# 07_mPCIe_4-8.net
KiCad netlist of a schematic drawn in Altium Designer
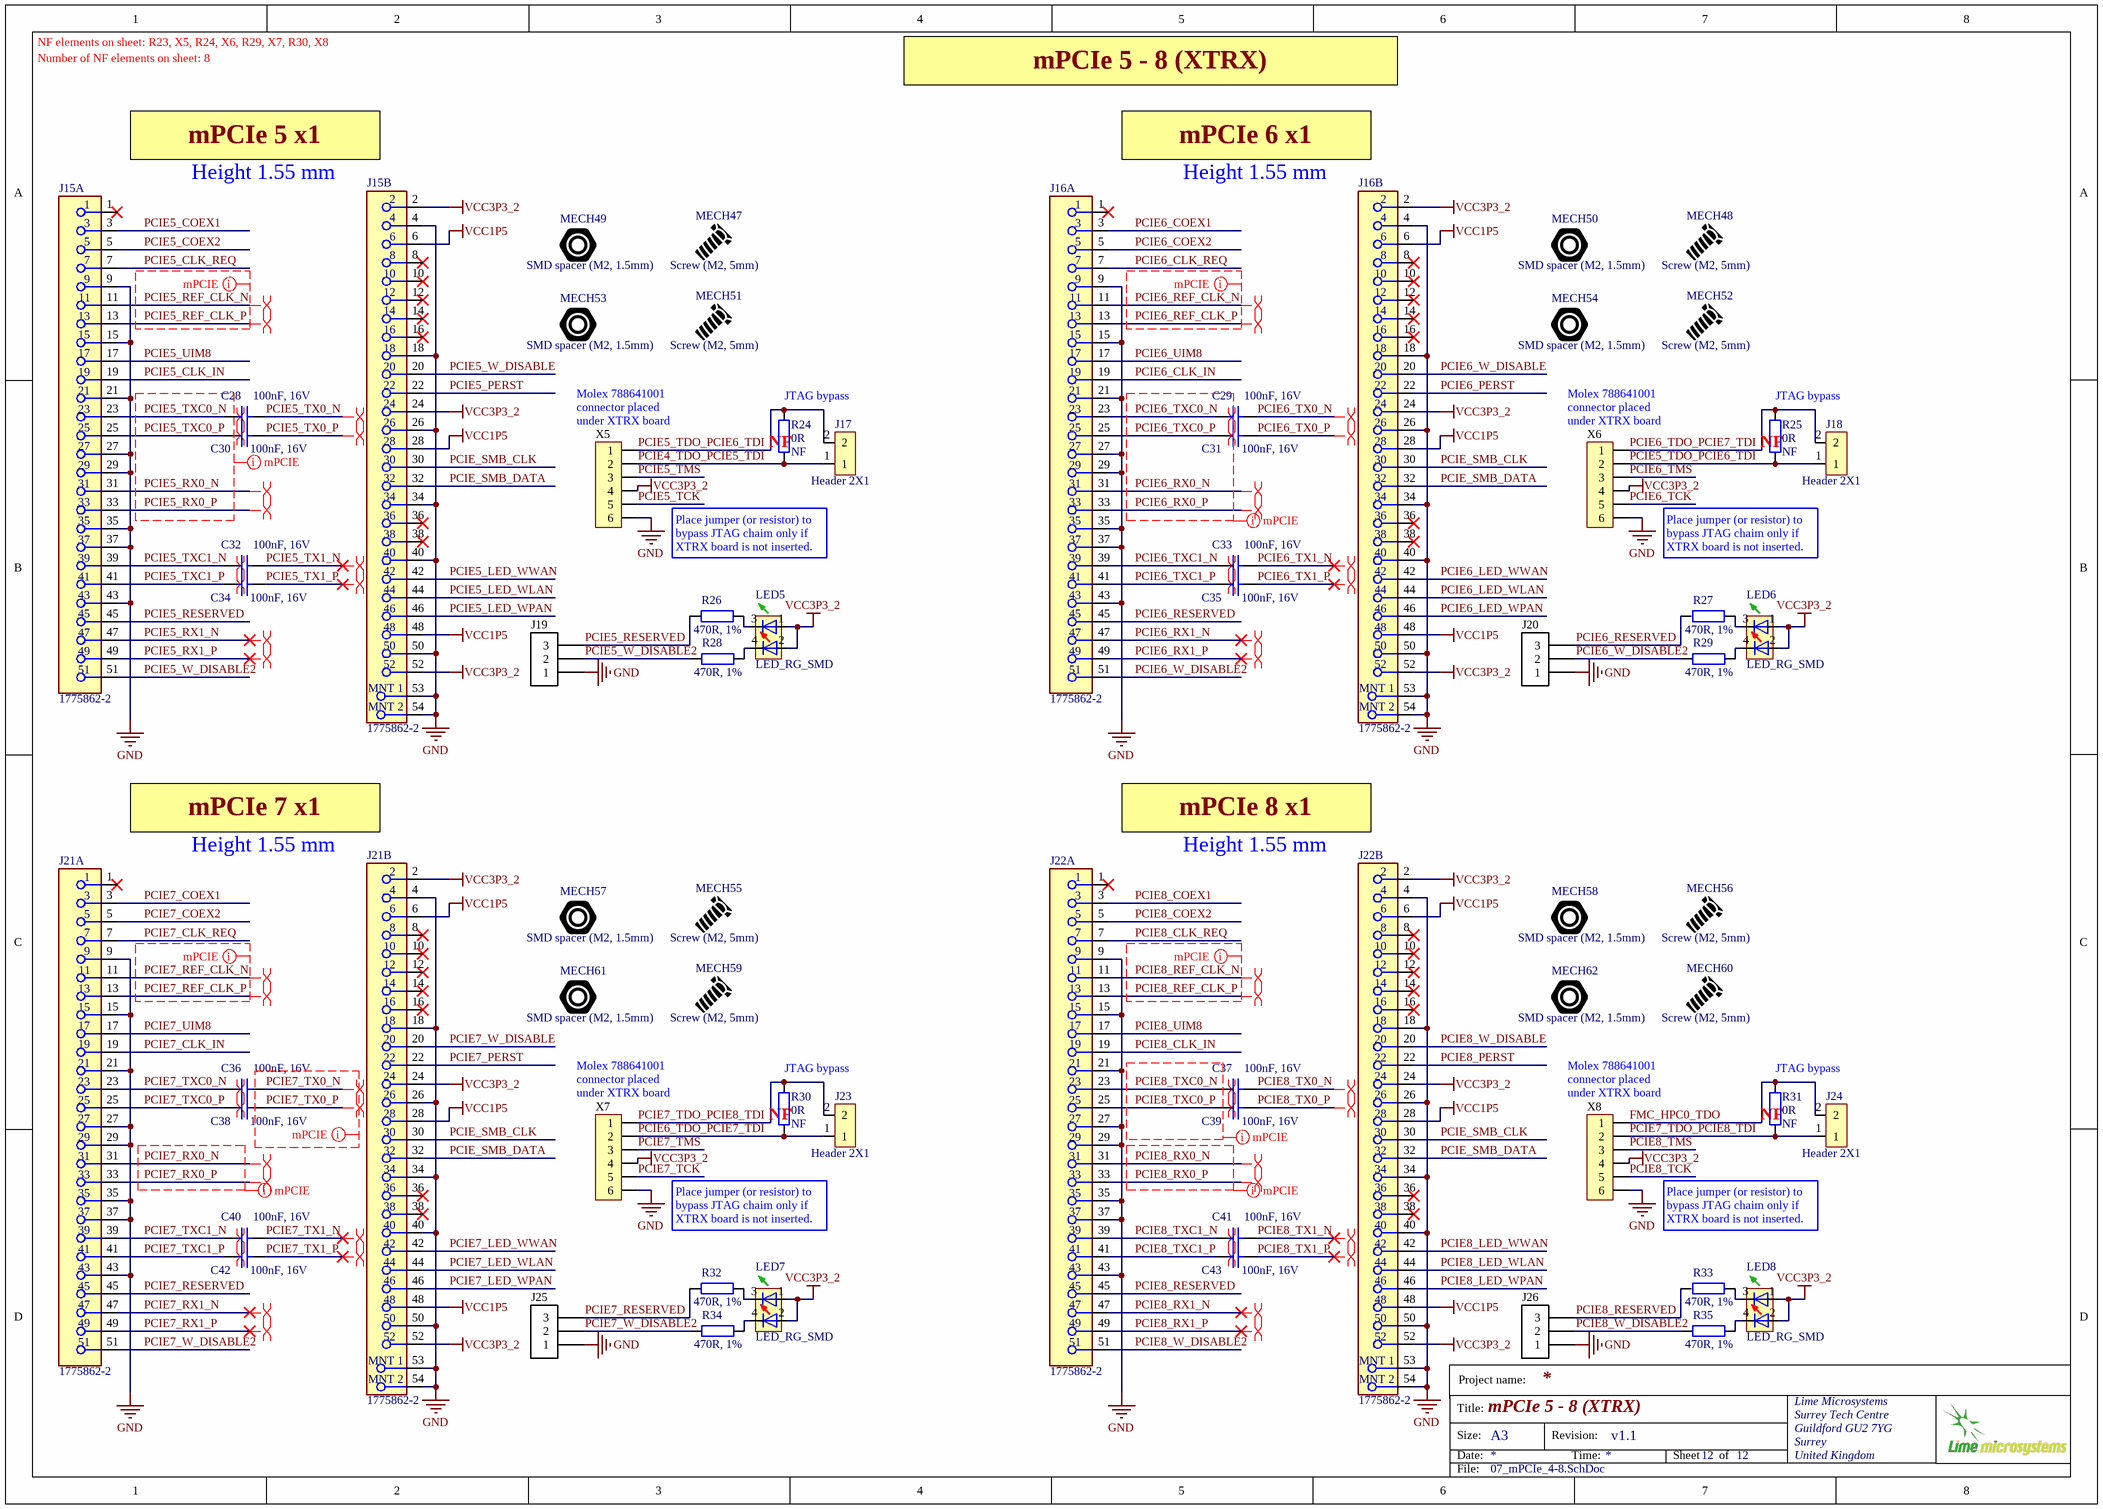
[diagram p0: 07_mPCIe_4-8.SchDoc]

(export (version "E")
  (design (tool "Eeschema 10.0.6"))
  (components
    (comp (ref "C28")
      (value "100nF, 16V")
      (footprint "CAP0402")
      (fields
        (field (name "MANUFACTURER") "Murata Electronics")
        (field (name "TOLERANCE") "10 %")
        (field (name "MANUFACTURER PART NUMBER") "GRM155R71C104KA88D")
      )
      (libsource (lib "LimeMicroAltiumLib_schLib") (part "Cap_0402"))
    )
    (comp (ref "C29")
      (value "100nF, 16V")
      (footprint "CAP0402")
      (fields
        (field (name "MANUFACTURER") "Murata Electronics")
        (field (name "TOLERANCE") "10 %")
        (field (name "MANUFACTURER PART NUMBER") "GRM155R71C104KA88D")
      )
      (libsource (lib "LimeMicroAltiumLib_schLib") (part "Cap_0402"))
    )
    (comp (ref "C30")
      (value "100nF, 16V")
      (footprint "CAP0402")
      (fields
        (field (name "MANUFACTURER") "Murata Electronics")
        (field (name "TOLERANCE") "10 %")
        (field (name "MANUFACTURER PART NUMBER") "GRM155R71C104KA88D")
      )
      (libsource (lib "LimeMicroAltiumLib_schLib") (part "Cap_0402"))
    )
    (comp (ref "C31")
      (value "100nF, 16V")
      (footprint "CAP0402")
      (fields
        (field (name "MANUFACTURER") "Murata Electronics")
        (field (name "TOLERANCE") "10 %")
        (field (name "MANUFACTURER PART NUMBER") "GRM155R71C104KA88D")
      )
      (libsource (lib "LimeMicroAltiumLib_schLib") (part "Cap_0402"))
    )
    (comp (ref "C32")
      (value "100nF, 16V")
      (footprint "CAP0402")
      (fields
        (field (name "MANUFACTURER") "Murata Electronics")
        (field (name "TOLERANCE") "10 %")
        (field (name "MANUFACTURER PART NUMBER") "GRM155R71C104KA88D")
      )
      (libsource (lib "LimeMicroAltiumLib_schLib") (part "Cap_0402"))
    )
    (comp (ref "C33")
      (value "100nF, 16V")
      (footprint "CAP0402")
      (fields
        (field (name "MANUFACTURER") "Murata Electronics")
        (field (name "TOLERANCE") "10 %")
        (field (name "MANUFACTURER PART NUMBER") "GRM155R71C104KA88D")
      )
      (libsource (lib "LimeMicroAltiumLib_schLib") (part "Cap_0402"))
    )
    (comp (ref "C34")
      (value "100nF, 16V")
      (footprint "CAP0402")
      (fields
        (field (name "MANUFACTURER") "Murata Electronics")
        (field (name "TOLERANCE") "10 %")
        (field (name "MANUFACTURER PART NUMBER") "GRM155R71C104KA88D")
      )
      (libsource (lib "LimeMicroAltiumLib_schLib") (part "Cap_0402"))
    )
    (comp (ref "C35")
      (value "100nF, 16V")
      (footprint "CAP0402")
      (fields
        (field (name "MANUFACTURER") "Murata Electronics")
        (field (name "TOLERANCE") "10 %")
        (field (name "MANUFACTURER PART NUMBER") "GRM155R71C104KA88D")
      )
      (libsource (lib "LimeMicroAltiumLib_schLib") (part "Cap_0402"))
    )
    (comp (ref "C36")
      (value "100nF, 16V")
      (footprint "CAP0402")
      (fields
        (field (name "MANUFACTURER") "Murata Electronics")
        (field (name "TOLERANCE") "10 %")
        (field (name "MANUFACTURER PART NUMBER") "GRM155R71C104KA88D")
      )
      (libsource (lib "LimeMicroAltiumLib_schLib") (part "Cap_0402"))
    )
    (comp (ref "C37")
      (value "100nF, 16V")
      (footprint "CAP0402")
      (fields
        (field (name "MANUFACTURER") "Murata Electronics")
        (field (name "TOLERANCE") "10 %")
        (field (name "MANUFACTURER PART NUMBER") "GRM155R71C104KA88D")
      )
      (libsource (lib "LimeMicroAltiumLib_schLib") (part "Cap_0402"))
    )
    (comp (ref "C38")
      (value "100nF, 16V")
      (footprint "CAP0402")
      (fields
        (field (name "MANUFACTURER") "Murata Electronics")
        (field (name "TOLERANCE") "10 %")
        (field (name "MANUFACTURER PART NUMBER") "GRM155R71C104KA88D")
      )
      (libsource (lib "LimeMicroAltiumLib_schLib") (part "Cap_0402"))
    )
    (comp (ref "C39")
      (value "100nF, 16V")
      (footprint "CAP0402")
      (fields
        (field (name "MANUFACTURER") "Murata Electronics")
        (field (name "TOLERANCE") "10 %")
        (field (name "MANUFACTURER PART NUMBER") "GRM155R71C104KA88D")
      )
      (libsource (lib "LimeMicroAltiumLib_schLib") (part "Cap_0402"))
    )
    (comp (ref "C40")
      (value "100nF, 16V")
      (footprint "CAP0402")
      (fields
        (field (name "MANUFACTURER") "Murata Electronics")
        (field (name "TOLERANCE") "10 %")
        (field (name "MANUFACTURER PART NUMBER") "GRM155R71C104KA88D")
      )
      (libsource (lib "LimeMicroAltiumLib_schLib") (part "Cap_0402"))
    )
    (comp (ref "C41")
      (value "100nF, 16V")
      (footprint "CAP0402")
      (fields
        (field (name "MANUFACTURER") "Murata Electronics")
        (field (name "TOLERANCE") "10 %")
        (field (name "MANUFACTURER PART NUMBER") "GRM155R71C104KA88D")
      )
      (libsource (lib "LimeMicroAltiumLib_schLib") (part "Cap_0402"))
    )
    (comp (ref "C42")
      (value "100nF, 16V")
      (footprint "CAP0402")
      (fields
        (field (name "MANUFACTURER") "Murata Electronics")
        (field (name "TOLERANCE") "10 %")
        (field (name "MANUFACTURER PART NUMBER") "GRM155R71C104KA88D")
      )
      (libsource (lib "LimeMicroAltiumLib_schLib") (part "Cap_0402"))
    )
    (comp (ref "C43")
      (value "100nF, 16V")
      (footprint "CAP0402")
      (fields
        (field (name "MANUFACTURER") "Murata Electronics")
        (field (name "TOLERANCE") "10 %")
        (field (name "MANUFACTURER PART NUMBER") "GRM155R71C104KA88D")
      )
      (libsource (lib "LimeMicroAltiumLib_schLib") (part "Cap_0402"))
    )
    (comp (ref "J15")
      (value "1775862-2")
      (footprint "MiniPCIe_connector_XTRX")
      (description "CONN PCI EXP MINI FEMALE 52POS")
      (fields (field (name "MANUFACTURER") "JAE Electronics"))
      (libsource (lib "LimeMicroAltiumLib_schLib_r04") (part "MINI_PCIE_FEMALE"))
    )
    (comp (ref "J16")
      (value "1775862-2")
      (footprint "MiniPCIe_connector_XTRX")
      (description "CONN PCI EXP MINI FEMALE 52POS")
      (fields (field (name "MANUFACTURER") "JAE Electronics"))
      (libsource (lib "LimeMicroAltiumLib_schLib_r04") (part "MINI_PCIE_FEMALE"))
    )
    (comp (ref "J17")
      (value "Header 2X1")
      (footprint "HDR_1x2")
      (fields (field (name "MANUFACTURER") "3M"))
      (libsource (lib "LimeFPGAboard_schLib") (part "Jumper"))
    )
    (comp (ref "J18")
      (value "Header 2X1")
      (footprint "HDR_1x2")
      (fields (field (name "MANUFACTURER") "3M"))
      (libsource (lib "LimeFPGAboard_schLib") (part "Jumper"))
    )
    (comp (ref "J19")
      (value "Header 3x1 pin")
      (footprint "HDR_1x3")
      (description "Header, 3-pin")
      (fields
        (field (name "MANUFACTURER PART NUMBER") "61300311121")
        (field (name "MANUFACTURER") "Wurth Electronics")
      )
      (libsource (lib "LimeMicroAltiumLib_schLib_r04") (part "Header3P"))
    )
    (comp (ref "J20")
      (value "Header 3x1 pin")
      (footprint "HDR_1x3")
      (description "Header, 3-pin")
      (fields
        (field (name "MANUFACTURER PART NUMBER") "61300311121")
        (field (name "MANUFACTURER") "Wurth Electronics")
      )
      (libsource (lib "LimeMicroAltiumLib_schLib_r04") (part "Header3P"))
    )
    (comp (ref "J21")
      (value "1775862-2")
      (footprint "MiniPCIe_connector_XTRX")
      (description "CONN PCI EXP MINI FEMALE 52POS")
      (fields (field (name "MANUFACTURER") "JAE Electronics"))
      (libsource (lib "LimeMicroAltiumLib_schLib_r04") (part "MINI_PCIE_FEMALE"))
    )
    (comp (ref "J22")
      (value "1775862-2")
      (footprint "MiniPCIe_connector_XTRX")
      (description "CONN PCI EXP MINI FEMALE 52POS")
      (fields (field (name "MANUFACTURER") "JAE Electronics"))
      (libsource (lib "LimeMicroAltiumLib_schLib_r04") (part "MINI_PCIE_FEMALE"))
    )
    (comp (ref "J23")
      (value "Header 2X1")
      (footprint "HDR_1x2")
      (fields (field (name "MANUFACTURER") "3M"))
      (libsource (lib "LimeFPGAboard_schLib") (part "Jumper"))
    )
    (comp (ref "J24")
      (value "Header 2X1")
      (footprint "HDR_1x2")
      (fields (field (name "MANUFACTURER") "3M"))
      (libsource (lib "LimeFPGAboard_schLib") (part "Jumper"))
    )
    (comp (ref "J25")
      (value "Header 3x1 pin")
      (footprint "HDR_1x3")
      (description "Header, 3-pin")
      (fields
        (field (name "MANUFACTURER PART NUMBER") "61300311121")
        (field (name "MANUFACTURER") "Wurth Electronics")
      )
      (libsource (lib "LimeMicroAltiumLib_schLib_r04") (part "Header3P"))
    )
    (comp (ref "J26")
      (value "Header 3x1 pin")
      (footprint "HDR_1x3")
      (description "Header, 3-pin")
      (fields
        (field (name "MANUFACTURER PART NUMBER") "61300311121")
        (field (name "MANUFACTURER") "Wurth Electronics")
      )
      (libsource (lib "LimeMicroAltiumLib_schLib_r04") (part "Header3P"))
    )
    (comp (ref "LED5")
      (value "LED_RG_SMD")
      (footprint "LED-2x0603")
      (fields (field (name "MANUFACTURER") "Avago Technologies US Inc."))
      (libsource (lib "LimeMicroAltiumLib_schLib") (part "LED_green_red_SMD"))
    )
    (comp (ref "LED6")
      (value "LED_RG_SMD")
      (footprint "LED-2x0603")
      (fields (field (name "MANUFACTURER") "Avago Technologies US Inc."))
      (libsource (lib "LimeMicroAltiumLib_schLib") (part "LED_green_red_SMD"))
    )
    (comp (ref "LED7")
      (value "LED_RG_SMD")
      (footprint "LED-2x0603")
      (fields (field (name "MANUFACTURER") "Avago Technologies US Inc."))
      (libsource (lib "LimeMicroAltiumLib_schLib") (part "LED_green_red_SMD"))
    )
    (comp (ref "LED8")
      (value "LED_RG_SMD")
      (footprint "LED-2x0603")
      (fields (field (name "MANUFACTURER") "Avago Technologies US Inc."))
      (libsource (lib "LimeMicroAltiumLib_schLib") (part "LED_green_red_SMD"))
    )
    (comp (ref "MECH47")
      (value "Screw (M2, 5mm)")
      (fields (field (name "MANUFACTURER") "B&F Fastener"))
      (libsource (lib "LimeMicroAltiumLib_schLib_r05") (part "Universal_mech_screw"))
    )
    (comp (ref "MECH48")
      (value "Screw (M2, 5mm)")
      (fields (field (name "MANUFACTURER") "B&F Fastener"))
      (libsource (lib "LimeMicroAltiumLib_schLib_r05") (part "Universal_mech_screw"))
    )
    (comp (ref "MECH49")
      (value "SMD spacer (M2, 1.5mm)")
      (fields (field (name "MANUFACTURER") "Wurth Electronics"))
      (libsource (lib "LimeMicroAltiumLib_schLib_r05") (part "Universal_mech_nut"))
    )
    (comp (ref "MECH50")
      (value "SMD spacer (M2, 1.5mm)")
      (fields (field (name "MANUFACTURER") "Wurth Electronics"))
      (libsource (lib "LimeMicroAltiumLib_schLib_r05") (part "Universal_mech_nut"))
    )
    (comp (ref "MECH51")
      (value "Screw (M2, 5mm)")
      (fields (field (name "MANUFACTURER") "B&F Fastener"))
      (libsource (lib "LimeMicroAltiumLib_schLib_r05") (part "Universal_mech_screw"))
    )
    (comp (ref "MECH52")
      (value "Screw (M2, 5mm)")
      (fields (field (name "MANUFACTURER") "B&F Fastener"))
      (libsource (lib "LimeMicroAltiumLib_schLib_r05") (part "Universal_mech_screw"))
    )
    (comp (ref "MECH53")
      (value "SMD spacer (M2, 1.5mm)")
      (fields (field (name "MANUFACTURER") "Wurth Electronics"))
      (libsource (lib "LimeMicroAltiumLib_schLib_r05") (part "Universal_mech_nut"))
    )
    (comp (ref "MECH54")
      (value "SMD spacer (M2, 1.5mm)")
      (fields (field (name "MANUFACTURER") "Wurth Electronics"))
      (libsource (lib "LimeMicroAltiumLib_schLib_r05") (part "Universal_mech_nut"))
    )
    (comp (ref "MECH55")
      (value "Screw (M2, 5mm)")
      (fields (field (name "MANUFACTURER") "B&F Fastener"))
      (libsource (lib "LimeMicroAltiumLib_schLib_r05") (part "Universal_mech_screw"))
    )
    (comp (ref "MECH56")
      (value "Screw (M2, 5mm)")
      (fields (field (name "MANUFACTURER") "B&F Fastener"))
      (libsource (lib "LimeMicroAltiumLib_schLib_r05") (part "Universal_mech_screw"))
    )
    (comp (ref "MECH57")
      (value "SMD spacer (M2, 1.5mm)")
      (fields (field (name "MANUFACTURER") "Wurth Electronics"))
      (libsource (lib "LimeMicroAltiumLib_schLib_r05") (part "Universal_mech_nut"))
    )
    (comp (ref "MECH58")
      (value "SMD spacer (M2, 1.5mm)")
      (fields (field (name "MANUFACTURER") "Wurth Electronics"))
      (libsource (lib "LimeMicroAltiumLib_schLib_r05") (part "Universal_mech_nut"))
    )
    (comp (ref "MECH59")
      (value "Screw (M2, 5mm)")
      (fields (field (name "MANUFACTURER") "B&F Fastener"))
      (libsource (lib "LimeMicroAltiumLib_schLib_r05") (part "Universal_mech_screw"))
    )
    (comp (ref "MECH60")
      (value "Screw (M2, 5mm)")
      (fields (field (name "MANUFACTURER") "B&F Fastener"))
      (libsource (lib "LimeMicroAltiumLib_schLib_r05") (part "Universal_mech_screw"))
    )
    (comp (ref "MECH61")
      (value "SMD spacer (M2, 1.5mm)")
      (fields (field (name "MANUFACTURER") "Wurth Electronics"))
      (libsource (lib "LimeMicroAltiumLib_schLib_r05") (part "Universal_mech_nut"))
    )
    (comp (ref "MECH62")
      (value "SMD spacer (M2, 1.5mm)")
      (fields (field (name "MANUFACTURER") "Wurth Electronics"))
      (libsource (lib "LimeMicroAltiumLib_schLib_r05") (part "Universal_mech_nut"))
    )
    (comp (ref "R24")
      (value "0R")
      (footprint "RES0402")
      (fields
        (field (name "ASSEMBLY INFO") "NF")
        (field (name "MANUFACTURER") "Yageo")
        (field (name "TOLERANCE") "Jumper")
      )
      (libsource (lib "LimeMicroAltiumLib_schLib") (part "Res_0402"))
    )
    (comp (ref "R25")
      (value "0R")
      (footprint "RES0402")
      (fields
        (field (name "ASSEMBLY INFO") "NF")
        (field (name "MANUFACTURER") "Yageo")
        (field (name "TOLERANCE") "Jumper")
      )
      (libsource (lib "LimeMicroAltiumLib_schLib") (part "Res_0402"))
    )
    (comp (ref "R26")
      (value "470R, 1%")
      (footprint "RES0402")
      (fields (field (name "TOLERANCE") "1%") (field (name "MANUFACTURER") "Yageo"))
      (libsource (lib "") (part "Res_0402_1"))
    )
    (comp (ref "R27")
      (value "470R, 1%")
      (footprint "RES0402")
      (fields (field (name "TOLERANCE") "1%") (field (name "MANUFACTURER") "Yageo"))
      (libsource (lib "") (part "Res_0402_1"))
    )
    (comp (ref "R28")
      (value "470R, 1%")
      (footprint "RES0402")
      (fields (field (name "TOLERANCE") "1%") (field (name "MANUFACTURER") "Yageo"))
      (libsource (lib "") (part "Res_0402_1"))
    )
    (comp (ref "R29")
      (value "470R, 1%")
      (footprint "RES0402")
      (fields (field (name "TOLERANCE") "1%") (field (name "MANUFACTURER") "Yageo"))
      (libsource (lib "") (part "Res_0402_1"))
    )
    (comp (ref "R30")
      (value "0R")
      (footprint "RES0402")
      (fields
        (field (name "ASSEMBLY INFO") "NF")
        (field (name "MANUFACTURER") "Yageo")
        (field (name "TOLERANCE") "Jumper")
      )
      (libsource (lib "LimeMicroAltiumLib_schLib") (part "Res_0402"))
    )
    (comp (ref "R31")
      (value "0R")
      (footprint "RES0402")
      (fields
        (field (name "ASSEMBLY INFO") "NF")
        (field (name "MANUFACTURER") "Yageo")
        (field (name "TOLERANCE") "Jumper")
      )
      (libsource (lib "LimeMicroAltiumLib_schLib") (part "Res_0402"))
    )
    (comp (ref "R32")
      (value "470R, 1%")
      (footprint "RES0402")
      (fields (field (name "TOLERANCE") "1%") (field (name "MANUFACTURER") "Yageo"))
      (libsource (lib "") (part "Res_0402_1"))
    )
    (comp (ref "R33")
      (value "470R, 1%")
      (footprint "RES0402")
      (fields (field (name "TOLERANCE") "1%") (field (name "MANUFACTURER") "Yageo"))
      (libsource (lib "") (part "Res_0402_1"))
    )
    (comp (ref "R34")
      (value "470R, 1%")
      (footprint "RES0402")
      (fields (field (name "TOLERANCE") "1%") (field (name "MANUFACTURER") "Yageo"))
      (libsource (lib "") (part "Res_0402_1"))
    )
    (comp (ref "R35")
      (value "470R, 1%")
      (footprint "RES0402")
      (fields (field (name "TOLERANCE") "1%") (field (name "MANUFACTURER") "Yageo"))
      (libsource (lib "") (part "Res_0402_1"))
    )
    (comp (ref "X5")
      (value "Molex 0788641001")
      (footprint "Molex_0788641001_spring_contacts_carrier")
      (description "Header, 6-pin")
      (fields (field (name "MANUFACTURER") "Molex"))
      (libsource (lib "LimeMicroAltiumLib_schLib_r04") (part "Molex_0788641001_spring_contacts"))
    )
    (comp (ref "X6")
      (value "Molex 0788641001")
      (footprint "Molex_0788641001_spring_contacts_carrier")
      (description "Header, 6-pin")
      (fields (field (name "MANUFACTURER") "Molex"))
      (libsource (lib "LimeMicroAltiumLib_schLib_r04") (part "Molex_0788641001_spring_contacts"))
    )
    (comp (ref "X7")
      (value "Molex 0788641001")
      (footprint "Molex_0788641001_spring_contacts_carrier")
      (description "Header, 6-pin")
      (fields (field (name "MANUFACTURER") "Molex"))
      (libsource (lib "LimeMicroAltiumLib_schLib_r04") (part "Molex_0788641001_spring_contacts"))
    )
    (comp (ref "X8")
      (value "Molex 0788641001")
      (footprint "Molex_0788641001_spring_contacts_carrier")
      (description "Header, 6-pin")
      (fields (field (name "MANUFACTURER") "Molex"))
      (libsource (lib "LimeMicroAltiumLib_schLib_r04") (part "Molex_0788641001_spring_contacts"))
    )
  )
  (nets
    (net (code "1") (name "/FMC_HPC0_TDO") (class "Default")
      (node (ref "J24") (pin "2") (pinfunction "2_2") (pintype "passive"))
      (node (ref "R31") (pin "1") (pinfunction "1_1") (pintype "passive"))
      (node (ref "X8") (pin "1") (pinfunction "1_1") (pintype "passive"))
    )
    (net (code "2") (name "/PCIE4_TDO_PCIE5_TDI") (class "Default")
      (node (ref "J17") (pin "1") (pinfunction "1_1") (pintype "passive"))
      (node (ref "R24") (pin "2") (pinfunction "2_2") (pintype "passive"))
      (node (ref "X5") (pin "2") (pinfunction "2_2") (pintype "passive"))
    )
    (net (code "3") (name "/PCIE5_CLK_IN") (class "Default")
      (node (ref "J15") (pin "19") (pinfunction "19_19") (pintype "passive"))
    )
    (net (code "4") (name "/PCIE5_CLK_REQ") (class "Default")
      (node (ref "J15") (pin "7") (pinfunction "7_7") (pintype "passive"))
    )
    (net (code "5") (name "/PCIE5_COEX1") (class "Default")
      (node (ref "J15") (pin "3") (pinfunction "3_3") (pintype "passive"))
    )
    (net (code "6") (name "/PCIE5_COEX2") (class "Default")
      (node (ref "J15") (pin "5") (pinfunction "5_5") (pintype "passive"))
    )
    (net (code "7") (name "/PCIE5_LED_WLAN") (class "Default")
      (node (ref "J15") (pin "44") (pinfunction "44_44") (pintype "passive"))
    )
    (net (code "8") (name "/PCIE5_LED_WPAN") (class "Default")
      (node (ref "J15") (pin "46") (pinfunction "46_46") (pintype "passive"))
    )
    (net (code "9") (name "/PCIE5_LED_WWAN") (class "Default")
      (node (ref "J15") (pin "42") (pinfunction "42_42") (pintype "passive"))
    )
    (net (code "10") (name "/PCIE5_PERST") (class "Default")
      (node (ref "J15") (pin "22") (pinfunction "22_22") (pintype "passive"))
    )
    (net (code "11") (name "/PCIE5_REF_CLK_N") (class "Default")
      (node (ref "J15") (pin "11") (pinfunction "11_11") (pintype "passive"))
    )
    (net (code "12") (name "/PCIE5_REF_CLK_P") (class "Default")
      (node (ref "J15") (pin "13") (pinfunction "13_13") (pintype "passive"))
    )
    (net (code "13") (name "/PCIE5_RESERVED") (class "Default")
      (node (ref "J15") (pin "45") (pinfunction "45_45") (pintype "passive"))
      (node (ref "J19") (pin "3") (pinfunction "3_3") (pintype "passive"))
      (node (ref "R26") (pin "2") (pinfunction "2_2") (pintype "passive"))
    )
    (net (code "14") (name "/PCIE5_RX0_N") (class "Default")
      (node (ref "J15") (pin "31") (pinfunction "31_31") (pintype "passive"))
    )
    (net (code "15") (name "/PCIE5_RX0_P") (class "Default")
      (node (ref "J15") (pin "33") (pinfunction "33_33") (pintype "passive"))
    )
    (net (code "16") (name "/PCIE5_RX1_N") (class "Default")
      (node (ref "J15") (pin "47") (pinfunction "47_47") (pintype "passive+no_connect"))
    )
    (net (code "17") (name "/PCIE5_RX1_P") (class "Default")
      (node (ref "J15") (pin "49") (pinfunction "49_49") (pintype "passive+no_connect"))
    )
    (net (code "18") (name "/PCIE5_TCK") (class "Default")
      (node (ref "X5") (pin "5") (pinfunction "5_5") (pintype "passive"))
    )
    (net (code "19") (name "/PCIE5_TDO_PCIE6_TDI") (class "Default")
      (node (ref "J17") (pin "2") (pinfunction "2_2") (pintype "passive"))
      (node (ref "J18") (pin "1") (pinfunction "1_1") (pintype "passive"))
      (node (ref "R24") (pin "1") (pinfunction "1_1") (pintype "passive"))
      (node (ref "R25") (pin "2") (pinfunction "2_2") (pintype "passive"))
      (node (ref "X5") (pin "1") (pinfunction "1_1") (pintype "passive"))
      (node (ref "X6") (pin "2") (pinfunction "2_2") (pintype "passive"))
    )
    (net (code "20") (name "/PCIE5_TMS") (class "Default")
      (node (ref "X5") (pin "3") (pinfunction "3_3") (pintype "passive"))
    )
    (net (code "21") (name "/PCIE5_TX0_N") (class "Default")
      (node (ref "C28") (pin "1") (pinfunction "1_1") (pintype "passive"))
    )
    (net (code "22") (name "/PCIE5_TX0_P") (class "Default")
      (node (ref "C30") (pin "1") (pinfunction "1_1") (pintype "passive"))
    )
    (net (code "23") (name "/PCIE5_TX1_N") (class "Default")
      (node (ref "C32") (pin "1") (pinfunction "1_1") (pintype "passive+no_connect"))
    )
    (net (code "24") (name "/PCIE5_TX1_P") (class "Default")
      (node (ref "C34") (pin "1") (pinfunction "1_1") (pintype "passive+no_connect"))
    )
    (net (code "25") (name "/PCIE5_TXC0_N") (class "Default")
      (node (ref "C28") (pin "2") (pinfunction "2_2") (pintype "passive"))
      (node (ref "J15") (pin "23") (pinfunction "23_23") (pintype "passive"))
    )
    (net (code "26") (name "/PCIE5_TXC0_P") (class "Default")
      (node (ref "C30") (pin "2") (pinfunction "2_2") (pintype "passive"))
      (node (ref "J15") (pin "25") (pinfunction "25_25") (pintype "passive"))
    )
    (net (code "27") (name "/PCIE5_TXC1_N") (class "Default")
      (node (ref "C32") (pin "2") (pinfunction "2_2") (pintype "passive"))
      (node (ref "J15") (pin "39") (pinfunction "39_39") (pintype "passive"))
    )
    (net (code "28") (name "/PCIE5_TXC1_P") (class "Default")
      (node (ref "C34") (pin "2") (pinfunction "2_2") (pintype "passive"))
      (node (ref "J15") (pin "41") (pinfunction "41_41") (pintype "passive"))
    )
    (net (code "29") (name "/PCIE5_UIM8") (class "Default")
      (node (ref "J15") (pin "17") (pinfunction "17_17") (pintype "passive"))
    )
    (net (code "30") (name "/PCIE5_W_DISABLE") (class "Default")
      (node (ref "J15") (pin "20") (pinfunction "20_20") (pintype "passive"))
    )
    (net (code "31") (name "/PCIE5_W_DISABLE2") (class "Default")
      (node (ref "J15") (pin "51") (pinfunction "51_51") (pintype "passive"))
      (node (ref "J19") (pin "2") (pinfunction "2_2") (pintype "passive"))
      (node (ref "R28") (pin "2") (pinfunction "2_2") (pintype "passive"))
    )
    (net (code "32") (name "/PCIE6_CLK_IN") (class "Default")
      (node (ref "J16") (pin "19") (pinfunction "19_19") (pintype "passive"))
    )
    (net (code "33") (name "/PCIE6_CLK_REQ") (class "Default")
      (node (ref "J16") (pin "7") (pinfunction "7_7") (pintype "passive"))
    )
    (net (code "34") (name "/PCIE6_COEX1") (class "Default")
      (node (ref "J16") (pin "3") (pinfunction "3_3") (pintype "passive"))
    )
    (net (code "35") (name "/PCIE6_COEX2") (class "Default")
      (node (ref "J16") (pin "5") (pinfunction "5_5") (pintype "passive"))
    )
    (net (code "36") (name "/PCIE6_LED_WLAN") (class "Default")
      (node (ref "J16") (pin "44") (pinfunction "44_44") (pintype "passive"))
    )
    (net (code "37") (name "/PCIE6_LED_WPAN") (class "Default")
      (node (ref "J16") (pin "46") (pinfunction "46_46") (pintype "passive"))
    )
    (net (code "38") (name "/PCIE6_LED_WWAN") (class "Default")
      (node (ref "J16") (pin "42") (pinfunction "42_42") (pintype "passive"))
    )
    (net (code "39") (name "/PCIE6_PERST") (class "Default")
      (node (ref "J16") (pin "22") (pinfunction "22_22") (pintype "passive"))
    )
    (net (code "40") (name "/PCIE6_REF_CLK_N") (class "Default")
      (node (ref "J16") (pin "11") (pinfunction "11_11") (pintype "passive"))
    )
    (net (code "41") (name "/PCIE6_REF_CLK_P") (class "Default")
      (node (ref "J16") (pin "13") (pinfunction "13_13") (pintype "passive"))
    )
    (net (code "42") (name "/PCIE6_RESERVED") (class "Default")
      (node (ref "J16") (pin "45") (pinfunction "45_45") (pintype "passive"))
      (node (ref "J20") (pin "3") (pinfunction "3_3") (pintype "passive"))
      (node (ref "R27") (pin "2") (pinfunction "2_2") (pintype "passive"))
    )
    (net (code "43") (name "/PCIE6_RX0_N") (class "Default")
      (node (ref "J16") (pin "31") (pinfunction "31_31") (pintype "passive"))
    )
    (net (code "44") (name "/PCIE6_RX0_P") (class "Default")
      (node (ref "J16") (pin "33") (pinfunction "33_33") (pintype "passive"))
    )
    (net (code "45") (name "/PCIE6_RX1_N") (class "Default")
      (node (ref "J16") (pin "47") (pinfunction "47_47") (pintype "passive+no_connect"))
    )
    (net (code "46") (name "/PCIE6_RX1_P") (class "Default")
      (node (ref "J16") (pin "49") (pinfunction "49_49") (pintype "passive+no_connect"))
    )
    (net (code "47") (name "/PCIE6_TCK") (class "Default")
      (node (ref "X6") (pin "5") (pinfunction "5_5") (pintype "passive"))
    )
    (net (code "48") (name "/PCIE6_TDO_PCIE7_TDI") (class "Default")
      (node (ref "J18") (pin "2") (pinfunction "2_2") (pintype "passive"))
      (node (ref "J23") (pin "1") (pinfunction "1_1") (pintype "passive"))
      (node (ref "R25") (pin "1") (pinfunction "1_1") (pintype "passive"))
      (node (ref "R30") (pin "2") (pinfunction "2_2") (pintype "passive"))
      (node (ref "X6") (pin "1") (pinfunction "1_1") (pintype "passive"))
      (node (ref "X7") (pin "2") (pinfunction "2_2") (pintype "passive"))
    )
    (net (code "49") (name "/PCIE6_TMS") (class "Default")
      (node (ref "X6") (pin "3") (pinfunction "3_3") (pintype "passive"))
    )
    (net (code "50") (name "/PCIE6_TX0_N") (class "Default")
      (node (ref "C29") (pin "1") (pinfunction "1_1") (pintype "passive"))
    )
    (net (code "51") (name "/PCIE6_TX0_P") (class "Default")
      (node (ref "C31") (pin "1") (pinfunction "1_1") (pintype "passive"))
    )
    (net (code "52") (name "/PCIE6_TX1_N") (class "Default")
      (node (ref "C33") (pin "1") (pinfunction "1_1") (pintype "passive+no_connect"))
    )
    (net (code "53") (name "/PCIE6_TX1_P") (class "Default")
      (node (ref "C35") (pin "1") (pinfunction "1_1") (pintype "passive+no_connect"))
    )
    (net (code "54") (name "/PCIE6_TXC0_N") (class "Default")
      (node (ref "C29") (pin "2") (pinfunction "2_2") (pintype "passive"))
      (node (ref "J16") (pin "23") (pinfunction "23_23") (pintype "passive"))
    )
    (net (code "55") (name "/PCIE6_TXC0_P") (class "Default")
      (node (ref "C31") (pin "2") (pinfunction "2_2") (pintype "passive"))
      (node (ref "J16") (pin "25") (pinfunction "25_25") (pintype "passive"))
    )
    (net (code "56") (name "/PCIE6_TXC1_N") (class "Default")
      (node (ref "C33") (pin "2") (pinfunction "2_2") (pintype "passive"))
      (node (ref "J16") (pin "39") (pinfunction "39_39") (pintype "passive"))
    )
    (net (code "57") (name "/PCIE6_TXC1_P") (class "Default")
      (node (ref "C35") (pin "2") (pinfunction "2_2") (pintype "passive"))
      (node (ref "J16") (pin "41") (pinfunction "41_41") (pintype "passive"))
    )
    (net (code "58") (name "/PCIE6_UIM8") (class "Default")
      (node (ref "J16") (pin "17") (pinfunction "17_17") (pintype "passive"))
    )
    (net (code "59") (name "/PCIE6_W_DISABLE") (class "Default")
      (node (ref "J16") (pin "20") (pinfunction "20_20") (pintype "passive"))
    )
    (net (code "60") (name "/PCIE6_W_DISABLE2") (class "Default")
      (node (ref "J16") (pin "51") (pinfunction "51_51") (pintype "passive"))
      (node (ref "J20") (pin "2") (pinfunction "2_2") (pintype "passive"))
      (node (ref "R29") (pin "2") (pinfunction "2_2") (pintype "passive"))
    )
    (net (code "61") (name "/PCIE7_CLK_IN") (class "Default")
      (node (ref "J21") (pin "19") (pinfunction "19_19") (pintype "passive"))
    )
    (net (code "62") (name "/PCIE7_CLK_REQ") (class "Default")
      (node (ref "J21") (pin "7") (pinfunction "7_7") (pintype "passive"))
    )
    (net (code "63") (name "/PCIE7_COEX1") (class "Default")
      (node (ref "J21") (pin "3") (pinfunction "3_3") (pintype "passive"))
    )
    (net (code "64") (name "/PCIE7_COEX2") (class "Default")
      (node (ref "J21") (pin "5") (pinfunction "5_5") (pintype "passive"))
    )
    (net (code "65") (name "/PCIE7_LED_WLAN") (class "Default")
      (node (ref "J21") (pin "44") (pinfunction "44_44") (pintype "passive"))
    )
    (net (code "66") (name "/PCIE7_LED_WPAN") (class "Default")
      (node (ref "J21") (pin "46") (pinfunction "46_46") (pintype "passive"))
    )
    (net (code "67") (name "/PCIE7_LED_WWAN") (class "Default")
      (node (ref "J21") (pin "42") (pinfunction "42_42") (pintype "passive"))
    )
    (net (code "68") (name "/PCIE7_PERST") (class "Default")
      (node (ref "J21") (pin "22") (pinfunction "22_22") (pintype "passive"))
    )
    (net (code "69") (name "/PCIE7_REF_CLK_N") (class "Default")
      (node (ref "J21") (pin "11") (pinfunction "11_11") (pintype "passive"))
    )
    (net (code "70") (name "/PCIE7_REF_CLK_P") (class "Default")
      (node (ref "J21") (pin "13") (pinfunction "13_13") (pintype "passive"))
    )
    (net (code "71") (name "/PCIE7_RESERVED") (class "Default")
      (node (ref "J21") (pin "45") (pinfunction "45_45") (pintype "passive"))
      (node (ref "J25") (pin "3") (pinfunction "3_3") (pintype "passive"))
      (node (ref "R32") (pin "2") (pinfunction "2_2") (pintype "passive"))
    )
    (net (code "72") (name "/PCIE7_RX0_N") (class "Default")
      (node (ref "J21") (pin "31") (pinfunction "31_31") (pintype "passive"))
    )
    (net (code "73") (name "/PCIE7_RX0_P") (class "Default")
      (node (ref "J21") (pin "33") (pinfunction "33_33") (pintype "passive"))
    )
    (net (code "74") (name "/PCIE7_RX1_N") (class "Default")
      (node (ref "J21") (pin "47") (pinfunction "47_47") (pintype "passive+no_connect"))
    )
    (net (code "75") (name "/PCIE7_RX1_P") (class "Default")
      (node (ref "J21") (pin "49") (pinfunction "49_49") (pintype "passive+no_connect"))
    )
    (net (code "76") (name "/PCIE7_TCK") (class "Default")
      (node (ref "X7") (pin "5") (pinfunction "5_5") (pintype "passive"))
    )
    (net (code "77") (name "/PCIE7_TDO_PCIE8_TDI") (class "Default")
      (node (ref "J23") (pin "2") (pinfunction "2_2") (pintype "passive"))
      (node (ref "J24") (pin "1") (pinfunction "1_1") (pintype "passive"))
      (node (ref "R30") (pin "1") (pinfunction "1_1") (pintype "passive"))
      (node (ref "R31") (pin "2") (pinfunction "2_2") (pintype "passive"))
      (node (ref "X7") (pin "1") (pinfunction "1_1") (pintype "passive"))
      (node (ref "X8") (pin "2") (pinfunction "2_2") (pintype "passive"))
    )
    (net (code "78") (name "/PCIE7_TMS") (class "Default")
      (node (ref "X7") (pin "3") (pinfunction "3_3") (pintype "passive"))
    )
    (net (code "79") (name "/PCIE7_TX0_N") (class "Default")
      (node (ref "C36") (pin "1") (pinfunction "1_1") (pintype "passive"))
    )
    (net (code "80") (name "/PCIE7_TX0_P") (class "Default")
      (node (ref "C38") (pin "1") (pinfunction "1_1") (pintype "passive"))
    )
    (net (code "81") (name "/PCIE7_TX1_N") (class "Default")
      (node (ref "C40") (pin "1") (pinfunction "1_1") (pintype "passive+no_connect"))
    )
    (net (code "82") (name "/PCIE7_TX1_P") (class "Default")
      (node (ref "C42") (pin "1") (pinfunction "1_1") (pintype "passive+no_connect"))
    )
    (net (code "83") (name "/PCIE7_TXC0_N") (class "Default")
      (node (ref "C36") (pin "2") (pinfunction "2_2") (pintype "passive"))
      (node (ref "J21") (pin "23") (pinfunction "23_23") (pintype "passive"))
    )
    (net (code "84") (name "/PCIE7_TXC0_P") (class "Default")
      (node (ref "C38") (pin "2") (pinfunction "2_2") (pintype "passive"))
      (node (ref "J21") (pin "25") (pinfunction "25_25") (pintype "passive"))
    )
    (net (code "85") (name "/PCIE7_TXC1_N") (class "Default")
      (node (ref "C40") (pin "2") (pinfunction "2_2") (pintype "passive"))
      (node (ref "J21") (pin "39") (pinfunction "39_39") (pintype "passive"))
    )
    (net (code "86") (name "/PCIE7_TXC1_P") (class "Default")
      (node (ref "C42") (pin "2") (pinfunction "2_2") (pintype "passive"))
      (node (ref "J21") (pin "41") (pinfunction "41_41") (pintype "passive"))
    )
    (net (code "87") (name "/PCIE7_UIM8") (class "Default")
      (node (ref "J21") (pin "17") (pinfunction "17_17") (pintype "passive"))
    )
    (net (code "88") (name "/PCIE7_W_DISABLE") (class "Default")
      (node (ref "J21") (pin "20") (pinfunction "20_20") (pintype "passive"))
    )
    (net (code "89") (name "/PCIE7_W_DISABLE2") (class "Default")
      (node (ref "J21") (pin "51") (pinfunction "51_51") (pintype "passive"))
      (node (ref "J25") (pin "2") (pinfunction "2_2") (pintype "passive"))
      (node (ref "R34") (pin "2") (pinfunction "2_2") (pintype "passive"))
    )
    (net (code "90") (name "/PCIE8_CLK_IN") (class "Default")
      (node (ref "J22") (pin "19") (pinfunction "19_19") (pintype "passive"))
    )
    (net (code "91") (name "/PCIE8_CLK_REQ") (class "Default")
      (node (ref "J22") (pin "7") (pinfunction "7_7") (pintype "passive"))
    )
    (net (code "92") (name "/PCIE8_COEX1") (class "Default")
      (node (ref "J22") (pin "3") (pinfunction "3_3") (pintype "passive"))
    )
    (net (code "93") (name "/PCIE8_COEX2") (class "Default")
      (node (ref "J22") (pin "5") (pinfunction "5_5") (pintype "passive"))
    )
    (net (code "94") (name "/PCIE8_LED_WLAN") (class "Default")
      (node (ref "J22") (pin "44") (pinfunction "44_44") (pintype "passive"))
    )
    (net (code "95") (name "/PCIE8_LED_WPAN") (class "Default")
      (node (ref "J22") (pin "46") (pinfunction "46_46") (pintype "passive"))
    )
    (net (code "96") (name "/PCIE8_LED_WWAN") (class "Default")
      (node (ref "J22") (pin "42") (pinfunction "42_42") (pintype "passive"))
    )
    (net (code "97") (name "/PCIE8_PERST") (class "Default")
      (node (ref "J22") (pin "22") (pinfunction "22_22") (pintype "passive"))
    )
    (net (code "98") (name "/PCIE8_REF_CLK_N") (class "Default")
      (node (ref "J22") (pin "11") (pinfunction "11_11") (pintype "passive"))
    )
    (net (code "99") (name "/PCIE8_REF_CLK_P") (class "Default")
      (node (ref "J22") (pin "13") (pinfunction "13_13") (pintype "passive"))
    )
    (net (code "100") (name "/PCIE8_RESERVED") (class "Default")
      (node (ref "J22") (pin "45") (pinfunction "45_45") (pintype "passive"))
      (node (ref "J26") (pin "3") (pinfunction "3_3") (pintype "passive"))
      (node (ref "R33") (pin "2") (pinfunction "2_2") (pintype "passive"))
    )
    (net (code "101") (name "/PCIE8_RX0_N") (class "Default")
      (node (ref "J22") (pin "31") (pinfunction "31_31") (pintype "passive"))
    )
    (net (code "102") (name "/PCIE8_RX0_P") (class "Default")
      (node (ref "J22") (pin "33") (pinfunction "33_33") (pintype "passive"))
    )
    (net (code "103") (name "/PCIE8_RX1_N") (class "Default")
      (node (ref "J22") (pin "47") (pinfunction "47_47") (pintype "passive+no_connect"))
    )
    (net (code "104") (name "/PCIE8_RX1_P") (class "Default")
      (node (ref "J22") (pin "49") (pinfunction "49_49") (pintype "passive+no_connect"))
    )
    (net (code "105") (name "/PCIE8_TCK") (class "Default")
      (node (ref "X8") (pin "5") (pinfunction "5_5") (pintype "passive"))
    )
    (net (code "106") (name "/PCIE8_TMS") (class "Default")
      (node (ref "X8") (pin "3") (pinfunction "3_3") (pintype "passive"))
    )
    (net (code "107") (name "/PCIE8_TX0_N") (class "Default")
      (node (ref "C37") (pin "1") (pinfunction "1_1") (pintype "passive"))
    )
    (net (code "108") (name "/PCIE8_TX0_P") (class "Default")
      (node (ref "C39") (pin "1") (pinfunction "1_1") (pintype "passive"))
    )
    (net (code "109") (name "/PCIE8_TX1_N") (class "Default")
      (node (ref "C41") (pin "1") (pinfunction "1_1") (pintype "passive+no_connect"))
    )
    (net (code "110") (name "/PCIE8_TX1_P") (class "Default")
      (node (ref "C43") (pin "1") (pinfunction "1_1") (pintype "passive+no_connect"))
    )
    (net (code "111") (name "/PCIE8_TXC0_N") (class "Default")
      (node (ref "C37") (pin "2") (pinfunction "2_2") (pintype "passive"))
      (node (ref "J22") (pin "23") (pinfunction "23_23") (pintype "passive"))
    )
    (net (code "112") (name "/PCIE8_TXC0_P") (class "Default")
      (node (ref "C39") (pin "2") (pinfunction "2_2") (pintype "passive"))
      (node (ref "J22") (pin "25") (pinfunction "25_25") (pintype "passive"))
    )
    (net (code "113") (name "/PCIE8_TXC1_N") (class "Default")
      (node (ref "C41") (pin "2") (pinfunction "2_2") (pintype "passive"))
      (node (ref "J22") (pin "39") (pinfunction "39_39") (pintype "passive"))
    )
    (net (code "114") (name "/PCIE8_TXC1_P") (class "Default")
      (node (ref "C43") (pin "2") (pinfunction "2_2") (pintype "passive"))
      (node (ref "J22") (pin "41") (pinfunction "41_41") (pintype "passive"))
    )
    (net (code "115") (name "/PCIE8_UIM8") (class "Default")
      (node (ref "J22") (pin "17") (pinfunction "17_17") (pintype "passive"))
    )
    (net (code "116") (name "/PCIE8_W_DISABLE") (class "Default")
      (node (ref "J22") (pin "20") (pinfunction "20_20") (pintype "passive"))
    )
    (net (code "117") (name "/PCIE8_W_DISABLE2") (class "Default")
      (node (ref "J22") (pin "51") (pinfunction "51_51") (pintype "passive"))
      (node (ref "J26") (pin "2") (pinfunction "2_2") (pintype "passive"))
      (node (ref "R35") (pin "2") (pinfunction "2_2") (pintype "passive"))
    )
    (net (code "118") (name "/PCIE_SMB_CLK") (class "Default")
      (node (ref "J15") (pin "30") (pinfunction "30_30") (pintype "passive"))
      (node (ref "J16") (pin "30") (pinfunction "30_30") (pintype "passive"))
      (node (ref "J21") (pin "30") (pinfunction "30_30") (pintype "passive"))
      (node (ref "J22") (pin "30") (pinfunction "30_30") (pintype "passive"))
    )
    (net (code "119") (name "/PCIE_SMB_DATA") (class "Default")
      (node (ref "J15") (pin "32") (pinfunction "32_32") (pintype "passive"))
      (node (ref "J16") (pin "32") (pinfunction "32_32") (pintype "passive"))
      (node (ref "J21") (pin "32") (pinfunction "32_32") (pintype "passive"))
      (node (ref "J22") (pin "32") (pinfunction "32_32") (pintype "passive"))
    )
    (net (code "120") (name "GND") (class "Default")
      (node (ref "J15") (pin "15") (pinfunction "15_15") (pintype "passive"))
      (node (ref "J15") (pin "18") (pinfunction "18_18") (pintype "passive"))
      (node (ref "J15") (pin "21") (pinfunction "21_21") (pintype "passive"))
      (node (ref "J15") (pin "26") (pinfunction "26_26") (pintype "passive"))
      (node (ref "J15") (pin "27") (pinfunction "27_27") (pintype "passive"))
      (node (ref "J15") (pin "29") (pinfunction "29_29") (pintype "passive"))
      (node (ref "J15") (pin "34") (pinfunction "34_34") (pintype "passive"))
      (node (ref "J15") (pin "35") (pinfunction "35_35") (pintype "passive"))
      (node (ref "J15") (pin "37") (pinfunction "37_37") (pintype "passive"))
      (node (ref "J15") (pin "4") (pinfunction "4_4") (pintype "passive"))
      (node (ref "J15") (pin "40") (pinfunction "40_40") (pintype "passive"))
      (node (ref "J15") (pin "43") (pinfunction "43_43") (pintype "passive"))
      (node (ref "J15") (pin "50") (pinfunction "50_50") (pintype "passive"))
      (node (ref "J15") (pin "53") (pinfunction "MNT_1_53") (pintype "passive"))
      (node (ref "J15") (pin "54") (pinfunction "MNT_2_54") (pintype "passive"))
      (node (ref "J15") (pin "9") (pinfunction "9_9") (pintype "passive"))
      (node (ref "J16") (pin "15") (pinfunction "15_15") (pintype "passive"))
      (node (ref "J16") (pin "18") (pinfunction "18_18") (pintype "passive"))
      (node (ref "J16") (pin "21") (pinfunction "21_21") (pintype "passive"))
      (node (ref "J16") (pin "26") (pinfunction "26_26") (pintype "passive"))
      (node (ref "J16") (pin "27") (pinfunction "27_27") (pintype "passive"))
      (node (ref "J16") (pin "29") (pinfunction "29_29") (pintype "passive"))
      (node (ref "J16") (pin "34") (pinfunction "34_34") (pintype "passive"))
      (node (ref "J16") (pin "35") (pinfunction "35_35") (pintype "passive"))
      (node (ref "J16") (pin "37") (pinfunction "37_37") (pintype "passive"))
      (node (ref "J16") (pin "4") (pinfunction "4_4") (pintype "passive"))
      (node (ref "J16") (pin "40") (pinfunction "40_40") (pintype "passive"))
      (node (ref "J16") (pin "43") (pinfunction "43_43") (pintype "passive"))
      (node (ref "J16") (pin "50") (pinfunction "50_50") (pintype "passive"))
      (node (ref "J16") (pin "53") (pinfunction "MNT_1_53") (pintype "passive"))
      (node (ref "J16") (pin "54") (pinfunction "MNT_2_54") (pintype "passive"))
      (node (ref "J16") (pin "9") (pinfunction "9_9") (pintype "passive"))
      (node (ref "J19") (pin "1") (pinfunction "1_1") (pintype "passive"))
      (node (ref "J20") (pin "1") (pinfunction "1_1") (pintype "passive"))
      (node (ref "J21") (pin "15") (pinfunction "15_15") (pintype "passive"))
      (node (ref "J21") (pin "18") (pinfunction "18_18") (pintype "passive"))
      (node (ref "J21") (pin "21") (pinfunction "21_21") (pintype "passive"))
      (node (ref "J21") (pin "26") (pinfunction "26_26") (pintype "passive"))
      (node (ref "J21") (pin "27") (pinfunction "27_27") (pintype "passive"))
      (node (ref "J21") (pin "29") (pinfunction "29_29") (pintype "passive"))
      (node (ref "J21") (pin "34") (pinfunction "34_34") (pintype "passive"))
      (node (ref "J21") (pin "35") (pinfunction "35_35") (pintype "passive"))
      (node (ref "J21") (pin "37") (pinfunction "37_37") (pintype "passive"))
      (node (ref "J21") (pin "4") (pinfunction "4_4") (pintype "passive"))
      (node (ref "J21") (pin "40") (pinfunction "40_40") (pintype "passive"))
      (node (ref "J21") (pin "43") (pinfunction "43_43") (pintype "passive"))
      (node (ref "J21") (pin "50") (pinfunction "50_50") (pintype "passive"))
      (node (ref "J21") (pin "53") (pinfunction "MNT_1_53") (pintype "passive"))
      (node (ref "J21") (pin "54") (pinfunction "MNT_2_54") (pintype "passive"))
      (node (ref "J21") (pin "9") (pinfunction "9_9") (pintype "passive"))
      (node (ref "J22") (pin "15") (pinfunction "15_15") (pintype "passive"))
      (node (ref "J22") (pin "18") (pinfunction "18_18") (pintype "passive"))
      (node (ref "J22") (pin "21") (pinfunction "21_21") (pintype "passive"))
      (node (ref "J22") (pin "26") (pinfunction "26_26") (pintype "passive"))
      (node (ref "J22") (pin "27") (pinfunction "27_27") (pintype "passive"))
      (node (ref "J22") (pin "29") (pinfunction "29_29") (pintype "passive"))
      (node (ref "J22") (pin "34") (pinfunction "34_34") (pintype "passive"))
      (node (ref "J22") (pin "35") (pinfunction "35_35") (pintype "passive"))
      (node (ref "J22") (pin "37") (pinfunction "37_37") (pintype "passive"))
      (node (ref "J22") (pin "4") (pinfunction "4_4") (pintype "passive"))
      (node (ref "J22") (pin "40") (pinfunction "40_40") (pintype "passive"))
      (node (ref "J22") (pin "43") (pinfunction "43_43") (pintype "passive"))
      (node (ref "J22") (pin "50") (pinfunction "50_50") (pintype "passive"))
      (node (ref "J22") (pin "53") (pinfunction "MNT_1_53") (pintype "passive"))
      (node (ref "J22") (pin "54") (pinfunction "MNT_2_54") (pintype "passive"))
      (node (ref "J22") (pin "9") (pinfunction "9_9") (pintype "passive"))
      (node (ref "J25") (pin "1") (pinfunction "1_1") (pintype "passive"))
      (node (ref "J26") (pin "1") (pinfunction "1_1") (pintype "passive"))
      (node (ref "X5") (pin "6") (pinfunction "6_6") (pintype "passive"))
      (node (ref "X6") (pin "6") (pinfunction "6_6") (pintype "passive"))
      (node (ref "X7") (pin "6") (pinfunction "6_6") (pintype "passive"))
      (node (ref "X8") (pin "6") (pinfunction "6_6") (pintype "passive"))
    )
    (net (code "121") (name "Net-(LED5-Pad3)") (class "Default")
      (node (ref "LED5") (pin "3") (pinfunction "3_3") (pintype "power_in"))
      (node (ref "R26") (pin "1") (pinfunction "1_1") (pintype "passive"))
    )
    (net (code "122") (name "Net-(LED5-Pad4)") (class "Default")
      (node (ref "LED5") (pin "4") (pinfunction "4_4") (pintype "power_in"))
      (node (ref "R28") (pin "1") (pinfunction "1_1") (pintype "passive"))
    )
    (net (code "123") (name "Net-(LED6-Pad3)") (class "Default")
      (node (ref "LED6") (pin "3") (pinfunction "3_3") (pintype "power_in"))
      (node (ref "R27") (pin "1") (pinfunction "1_1") (pintype "passive"))
    )
    (net (code "124") (name "Net-(LED6-Pad4)") (class "Default")
      (node (ref "LED6") (pin "4") (pinfunction "4_4") (pintype "power_in"))
      (node (ref "R29") (pin "1") (pinfunction "1_1") (pintype "passive"))
    )
    (net (code "125") (name "Net-(LED7-Pad3)") (class "Default")
      (node (ref "LED7") (pin "3") (pinfunction "3_3") (pintype "power_in"))
      (node (ref "R32") (pin "1") (pinfunction "1_1") (pintype "passive"))
    )
    (net (code "126") (name "Net-(LED7-Pad4)") (class "Default")
      (node (ref "LED7") (pin "4") (pinfunction "4_4") (pintype "power_in"))
      (node (ref "R34") (pin "1") (pinfunction "1_1") (pintype "passive"))
    )
    (net (code "127") (name "Net-(LED8-Pad3)") (class "Default")
      (node (ref "LED8") (pin "3") (pinfunction "3_3") (pintype "power_in"))
      (node (ref "R33") (pin "1") (pinfunction "1_1") (pintype "passive"))
    )
    (net (code "128") (name "Net-(LED8-Pad4)") (class "Default")
      (node (ref "LED8") (pin "4") (pinfunction "4_4") (pintype "power_in"))
      (node (ref "R35") (pin "1") (pinfunction "1_1") (pintype "passive"))
    )
    (net (code "129") (name "VCC1P5") (class "Default")
      (node (ref "J15") (pin "28") (pinfunction "28_28") (pintype "passive"))
      (node (ref "J15") (pin "48") (pinfunction "48_48") (pintype "passive"))
      (node (ref "J15") (pin "6") (pinfunction "6_6") (pintype "passive"))
      (node (ref "J16") (pin "28") (pinfunction "28_28") (pintype "passive"))
      (node (ref "J16") (pin "48") (pinfunction "48_48") (pintype "passive"))
      (node (ref "J16") (pin "6") (pinfunction "6_6") (pintype "passive"))
      (node (ref "J21") (pin "28") (pinfunction "28_28") (pintype "passive"))
      (node (ref "J21") (pin "48") (pinfunction "48_48") (pintype "passive"))
      (node (ref "J21") (pin "6") (pinfunction "6_6") (pintype "passive"))
      (node (ref "J22") (pin "28") (pinfunction "28_28") (pintype "passive"))
      (node (ref "J22") (pin "48") (pinfunction "48_48") (pintype "passive"))
      (node (ref "J22") (pin "6") (pinfunction "6_6") (pintype "passive"))
    )
    (net (code "130") (name "VCC3P3_2") (class "Default")
      (node (ref "J15") (pin "2") (pinfunction "2_2") (pintype "passive"))
      (node (ref "J15") (pin "24") (pinfunction "24_24") (pintype "passive"))
      (node (ref "J15") (pin "52") (pinfunction "52_52") (pintype "passive"))
      (node (ref "J16") (pin "2") (pinfunction "2_2") (pintype "passive"))
      (node (ref "J16") (pin "24") (pinfunction "24_24") (pintype "passive"))
      (node (ref "J16") (pin "52") (pinfunction "52_52") (pintype "passive"))
      (node (ref "J21") (pin "2") (pinfunction "2_2") (pintype "passive"))
      (node (ref "J21") (pin "24") (pinfunction "24_24") (pintype "passive"))
      (node (ref "J21") (pin "52") (pinfunction "52_52") (pintype "passive"))
      (node (ref "J22") (pin "2") (pinfunction "2_2") (pintype "passive"))
      (node (ref "J22") (pin "24") (pinfunction "24_24") (pintype "passive"))
      (node (ref "J22") (pin "52") (pinfunction "52_52") (pintype "passive"))
      (node (ref "LED5") (pin "1") (pinfunction "1_1") (pintype "power_in"))
      (node (ref "LED5") (pin "2") (pinfunction "2_2") (pintype "power_in"))
      (node (ref "LED6") (pin "1") (pinfunction "1_1") (pintype "power_in"))
      (node (ref "LED6") (pin "2") (pinfunction "2_2") (pintype "power_in"))
      (node (ref "LED7") (pin "1") (pinfunction "1_1") (pintype "power_in"))
      (node (ref "LED7") (pin "2") (pinfunction "2_2") (pintype "power_in"))
      (node (ref "LED8") (pin "1") (pinfunction "1_1") (pintype "power_in"))
      (node (ref "LED8") (pin "2") (pinfunction "2_2") (pintype "power_in"))
      (node (ref "X5") (pin "4") (pinfunction "4_4") (pintype "passive"))
      (node (ref "X6") (pin "4") (pinfunction "4_4") (pintype "passive"))
      (node (ref "X7") (pin "4") (pinfunction "4_4") (pintype "passive"))
      (node (ref "X8") (pin "4") (pinfunction "4_4") (pintype "passive"))
    )
    (net (code "131") (name "unconnected-(J15-Pad1)") (class "Default")
      (node (ref "J15") (pin "1") (pinfunction "1_1") (pintype "passive+no_connect"))
    )
    (net (code "132") (name "unconnected-(J15-Pad8)") (class "Default")
      (node (ref "J15") (pin "8") (pinfunction "8_8") (pintype "passive+no_connect"))
    )
    (net (code "133") (name "unconnected-(J15-Pad10)") (class "Default")
      (node (ref "J15") (pin "10") (pinfunction "10_10") (pintype "passive+no_connect"))
    )
    (net (code "134") (name "unconnected-(J15-Pad12)") (class "Default")
      (node (ref "J15") (pin "12") (pinfunction "12_12") (pintype "passive+no_connect"))
    )
    (net (code "135") (name "unconnected-(J15-Pad14)") (class "Default")
      (node (ref "J15") (pin "14") (pinfunction "14_14") (pintype "passive+no_connect"))
    )
    (net (code "136") (name "unconnected-(J15-Pad16)") (class "Default")
      (node (ref "J15") (pin "16") (pinfunction "16_16") (pintype "passive+no_connect"))
    )
    (net (code "137") (name "unconnected-(J15-Pad36)") (class "Default")
      (node (ref "J15") (pin "36") (pinfunction "36_36") (pintype "passive+no_connect"))
    )
    (net (code "138") (name "unconnected-(J15-Pad38)") (class "Default")
      (node (ref "J15") (pin "38") (pinfunction "38_38") (pintype "passive+no_connect"))
    )
    (net (code "139") (name "unconnected-(J16-Pad1)") (class "Default")
      (node (ref "J16") (pin "1") (pinfunction "1_1") (pintype "passive+no_connect"))
    )
    (net (code "140") (name "unconnected-(J16-Pad8)") (class "Default")
      (node (ref "J16") (pin "8") (pinfunction "8_8") (pintype "passive+no_connect"))
    )
    (net (code "141") (name "unconnected-(J16-Pad10)") (class "Default")
      (node (ref "J16") (pin "10") (pinfunction "10_10") (pintype "passive+no_connect"))
    )
    (net (code "142") (name "unconnected-(J16-Pad12)") (class "Default")
      (node (ref "J16") (pin "12") (pinfunction "12_12") (pintype "passive+no_connect"))
    )
    (net (code "143") (name "unconnected-(J16-Pad14)") (class "Default")
      (node (ref "J16") (pin "14") (pinfunction "14_14") (pintype "passive+no_connect"))
    )
    (net (code "144") (name "unconnected-(J16-Pad16)") (class "Default")
      (node (ref "J16") (pin "16") (pinfunction "16_16") (pintype "passive+no_connect"))
    )
    (net (code "145") (name "unconnected-(J16-Pad36)") (class "Default")
      (node (ref "J16") (pin "36") (pinfunction "36_36") (pintype "passive+no_connect"))
    )
    (net (code "146") (name "unconnected-(J16-Pad38)") (class "Default")
      (node (ref "J16") (pin "38") (pinfunction "38_38") (pintype "passive+no_connect"))
    )
    (net (code "147") (name "unconnected-(J21-Pad1)") (class "Default")
      (node (ref "J21") (pin "1") (pinfunction "1_1") (pintype "passive+no_connect"))
    )
    (net (code "148") (name "unconnected-(J21-Pad8)") (class "Default")
      (node (ref "J21") (pin "8") (pinfunction "8_8") (pintype "passive+no_connect"))
    )
    (net (code "149") (name "unconnected-(J21-Pad10)") (class "Default")
      (node (ref "J21") (pin "10") (pinfunction "10_10") (pintype "passive+no_connect"))
    )
    (net (code "150") (name "unconnected-(J21-Pad12)") (class "Default")
      (node (ref "J21") (pin "12") (pinfunction "12_12") (pintype "passive+no_connect"))
    )
    (net (code "151") (name "unconnected-(J21-Pad14)") (class "Default")
      (node (ref "J21") (pin "14") (pinfunction "14_14") (pintype "passive+no_connect"))
    )
    (net (code "152") (name "unconnected-(J21-Pad16)") (class "Default")
      (node (ref "J21") (pin "16") (pinfunction "16_16") (pintype "passive+no_connect"))
    )
    (net (code "153") (name "unconnected-(J21-Pad36)") (class "Default")
      (node (ref "J21") (pin "36") (pinfunction "36_36") (pintype "passive+no_connect"))
    )
    (net (code "154") (name "unconnected-(J21-Pad38)") (class "Default")
      (node (ref "J21") (pin "38") (pinfunction "38_38") (pintype "passive+no_connect"))
    )
    (net (code "155") (name "unconnected-(J22-Pad1)") (class "Default")
      (node (ref "J22") (pin "1") (pinfunction "1_1") (pintype "passive+no_connect"))
    )
    (net (code "156") (name "unconnected-(J22-Pad8)") (class "Default")
      (node (ref "J22") (pin "8") (pinfunction "8_8") (pintype "passive+no_connect"))
    )
    (net (code "157") (name "unconnected-(J22-Pad10)") (class "Default")
      (node (ref "J22") (pin "10") (pinfunction "10_10") (pintype "passive+no_connect"))
    )
    (net (code "158") (name "unconnected-(J22-Pad12)") (class "Default")
      (node (ref "J22") (pin "12") (pinfunction "12_12") (pintype "passive+no_connect"))
    )
    (net (code "159") (name "unconnected-(J22-Pad14)") (class "Default")
      (node (ref "J22") (pin "14") (pinfunction "14_14") (pintype "passive+no_connect"))
    )
    (net (code "160") (name "unconnected-(J22-Pad16)") (class "Default")
      (node (ref "J22") (pin "16") (pinfunction "16_16") (pintype "passive+no_connect"))
    )
    (net (code "161") (name "unconnected-(J22-Pad36)") (class "Default")
      (node (ref "J22") (pin "36") (pinfunction "36_36") (pintype "passive+no_connect"))
    )
    (net (code "162") (name "unconnected-(J22-Pad38)") (class "Default")
      (node (ref "J22") (pin "38") (pinfunction "38_38") (pintype "passive+no_connect"))
    )
  )
)
